# 3X3LEDCube.net
KiCad netlist of a schematic drawn in EAGLE
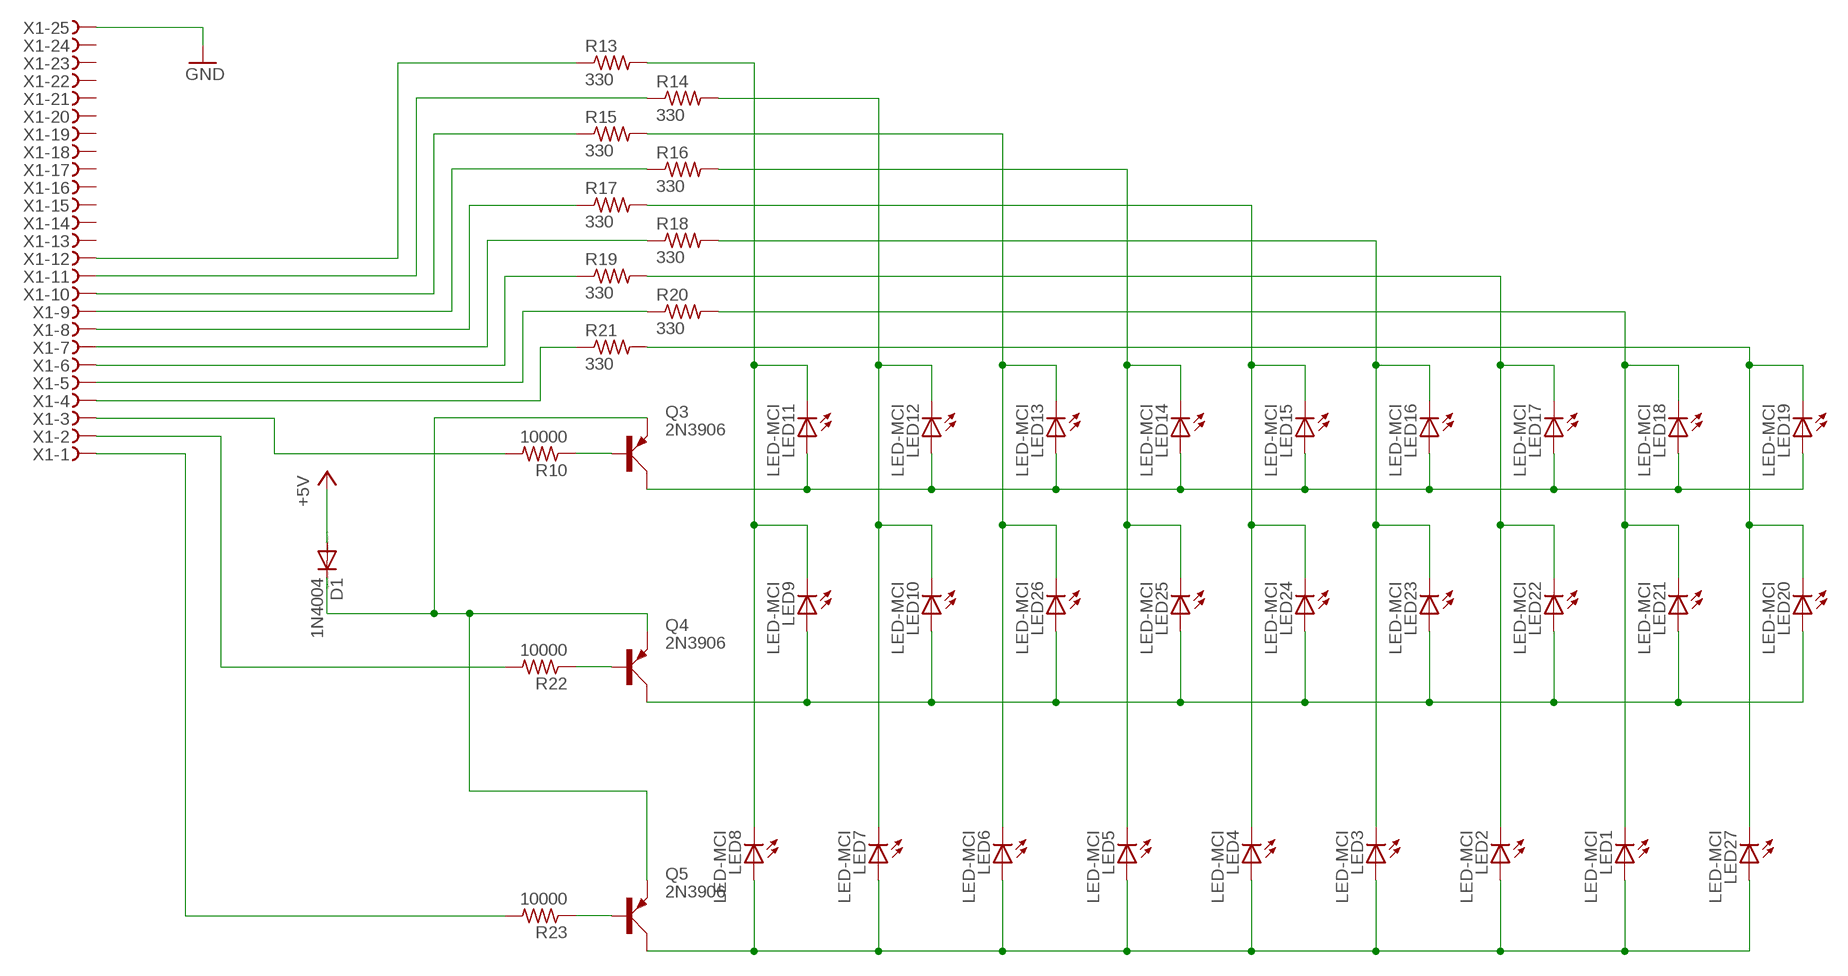
[diagram p0: schematic, sheet 1]

(export (version "E")
  (design (tool "Eeschema 10.0.6"))
  (components
    (comp (ref "D1")
      (value "1N4004")
      (footprint "eagle-import:DO41-10")
      (libsource (lib "eagle-import") (part "1N4004"))
    )
    (comp (ref "LED1")
      (value "LED-MCI")
      (footprint "eagle-import:LED-MCI")
      (libsource (lib "eagle-import") (part "LED-MCI"))
    )
    (comp (ref "LED2")
      (value "LED-MCI")
      (footprint "eagle-import:LED-MCI")
      (libsource (lib "eagle-import") (part "LED-MCI"))
    )
    (comp (ref "LED3")
      (value "LED-MCI")
      (footprint "eagle-import:LED-MCI")
      (libsource (lib "eagle-import") (part "LED-MCI"))
    )
    (comp (ref "LED4")
      (value "LED-MCI")
      (footprint "eagle-import:LED-MCI")
      (libsource (lib "eagle-import") (part "LED-MCI"))
    )
    (comp (ref "LED5")
      (value "LED-MCI")
      (footprint "eagle-import:LED-MCI")
      (libsource (lib "eagle-import") (part "LED-MCI"))
    )
    (comp (ref "LED6")
      (value "LED-MCI")
      (footprint "eagle-import:LED-MCI")
      (libsource (lib "eagle-import") (part "LED-MCI"))
    )
    (comp (ref "LED7")
      (value "LED-MCI")
      (footprint "eagle-import:LED-MCI")
      (libsource (lib "eagle-import") (part "LED-MCI"))
    )
    (comp (ref "LED8")
      (value "LED-MCI")
      (footprint "eagle-import:LED-MCI")
      (libsource (lib "eagle-import") (part "LED-MCI"))
    )
    (comp (ref "LED9")
      (value "LED-MCI")
      (footprint "eagle-import:LED-MCI")
      (libsource (lib "eagle-import") (part "LED-MCI"))
    )
    (comp (ref "LED10")
      (value "LED-MCI")
      (footprint "eagle-import:LED-MCI")
      (libsource (lib "eagle-import") (part "LED-MCI"))
    )
    (comp (ref "LED11")
      (value "LED-MCI")
      (footprint "eagle-import:LED-MCI")
      (libsource (lib "eagle-import") (part "LED-MCI"))
    )
    (comp (ref "LED12")
      (value "LED-MCI")
      (footprint "eagle-import:LED-MCI")
      (libsource (lib "eagle-import") (part "LED-MCI"))
    )
    (comp (ref "LED13")
      (value "LED-MCI")
      (footprint "eagle-import:LED-MCI")
      (libsource (lib "eagle-import") (part "LED-MCI"))
    )
    (comp (ref "LED14")
      (value "LED-MCI")
      (footprint "eagle-import:LED-MCI")
      (libsource (lib "eagle-import") (part "LED-MCI"))
    )
    (comp (ref "LED15")
      (value "LED-MCI")
      (footprint "eagle-import:LED-MCI")
      (libsource (lib "eagle-import") (part "LED-MCI"))
    )
    (comp (ref "LED16")
      (value "LED-MCI")
      (footprint "eagle-import:LED-MCI")
      (libsource (lib "eagle-import") (part "LED-MCI"))
    )
    (comp (ref "LED17")
      (value "LED-MCI")
      (footprint "eagle-import:LED-MCI")
      (libsource (lib "eagle-import") (part "LED-MCI"))
    )
    (comp (ref "LED18")
      (value "LED-MCI")
      (footprint "eagle-import:LED-MCI")
      (libsource (lib "eagle-import") (part "LED-MCI"))
    )
    (comp (ref "LED19")
      (value "LED-MCI")
      (footprint "eagle-import:LED-MCI")
      (libsource (lib "eagle-import") (part "LED-MCI"))
    )
    (comp (ref "LED20")
      (value "LED-MCI")
      (footprint "eagle-import:LED-MCI")
      (libsource (lib "eagle-import") (part "LED-MCI"))
    )
    (comp (ref "LED21")
      (value "LED-MCI")
      (footprint "eagle-import:LED-MCI")
      (libsource (lib "eagle-import") (part "LED-MCI"))
    )
    (comp (ref "LED22")
      (value "LED-MCI")
      (footprint "eagle-import:LED-MCI")
      (libsource (lib "eagle-import") (part "LED-MCI"))
    )
    (comp (ref "LED23")
      (value "LED-MCI")
      (footprint "eagle-import:LED-MCI")
      (libsource (lib "eagle-import") (part "LED-MCI"))
    )
    (comp (ref "LED24")
      (value "LED-MCI")
      (footprint "eagle-import:LED-MCI")
      (libsource (lib "eagle-import") (part "LED-MCI"))
    )
    (comp (ref "LED25")
      (value "LED-MCI")
      (footprint "eagle-import:LED-MCI")
      (libsource (lib "eagle-import") (part "LED-MCI"))
    )
    (comp (ref "LED26")
      (value "LED-MCI")
      (footprint "eagle-import:LED-MCI")
      (libsource (lib "eagle-import") (part "LED-MCI"))
    )
    (comp (ref "LED27")
      (value "LED-MCI")
      (footprint "eagle-import:LED-MCI")
      (libsource (lib "eagle-import") (part "LED-MCI"))
    )
    (comp (ref "Q3")
      (value "2N3906")
      (footprint "eagle-import:TO92D")
      (libsource (lib "eagle-import") (part "2N3906"))
    )
    (comp (ref "Q4")
      (value "2N3906")
      (footprint "eagle-import:TO92D")
      (libsource (lib "eagle-import") (part "2N3906"))
    )
    (comp (ref "Q5")
      (value "2N3906")
      (footprint "eagle-import:TO92D")
      (libsource (lib "eagle-import") (part "2N3906"))
    )
    (comp (ref "R10")
      (value "10000")
      (footprint "eagle-import:RESISTOR-MCI")
      (libsource (lib "eagle-import") (part "RESISTOR-MCI"))
    )
    (comp (ref "R13")
      (value "330")
      (footprint "eagle-import:RESISTOR-MCI")
      (libsource (lib "eagle-import") (part "RESISTOR-MCI"))
    )
    (comp (ref "R14")
      (value "330")
      (footprint "eagle-import:RESISTOR-MCI")
      (libsource (lib "eagle-import") (part "RESISTOR-MCI"))
    )
    (comp (ref "R15")
      (value "330")
      (footprint "eagle-import:RESISTOR-MCI")
      (libsource (lib "eagle-import") (part "RESISTOR-MCI"))
    )
    (comp (ref "R16")
      (value "330")
      (footprint "eagle-import:RESISTOR-MCI")
      (libsource (lib "eagle-import") (part "RESISTOR-MCI"))
    )
    (comp (ref "R17")
      (value "330")
      (footprint "eagle-import:RESISTOR-MCI")
      (libsource (lib "eagle-import") (part "RESISTOR-MCI"))
    )
    (comp (ref "R18")
      (value "330")
      (footprint "eagle-import:RESISTOR-MCI")
      (libsource (lib "eagle-import") (part "RESISTOR-MCI"))
    )
    (comp (ref "R19")
      (value "330")
      (footprint "eagle-import:RESISTOR-MCI")
      (libsource (lib "eagle-import") (part "RESISTOR-MCI"))
    )
    (comp (ref "R20")
      (value "330")
      (footprint "eagle-import:RESISTOR-MCI")
      (libsource (lib "eagle-import") (part "RESISTOR-MCI"))
    )
    (comp (ref "R21")
      (value "330")
      (footprint "eagle-import:RESISTOR-MCI")
      (libsource (lib "eagle-import") (part "RESISTOR-MCI"))
    )
    (comp (ref "R22")
      (value "10000")
      (footprint "eagle-import:RESISTOR-MCI")
      (libsource (lib "eagle-import") (part "RESISTOR-MCI"))
    )
    (comp (ref "R23")
      (value "10000")
      (footprint "eagle-import:RESISTOR-MCI")
      (libsource (lib "eagle-import") (part "RESISTOR-MCI"))
    )
    (comp (ref "X1")
      (value "F25.590S")
      (footprint "eagle-import:177-025-FEMALE")
      (libsource (lib "eagle-import") (part "F25?S.590"))
    )
  )
  (nets
    (net (code "1") (name "+5V") (class "Default")
      (node (ref "D1") (pin "A") (pinfunction "A_A") (pintype "passive"))
    )
    (net (code "2") (name "GND") (class "Default")
      (node (ref "X1") (pin "25") (pinfunction "F_25") (pintype "passive"))
    )
    (net (code "3") (name "Net-(D1-PadC)") (class "Default")
      (node (ref "D1") (pin "C") (pinfunction "C_C") (pintype "passive"))
      (node (ref "Q3") (pin "E") (pinfunction "E_E") (pintype "passive"))
      (node (ref "Q4") (pin "E") (pinfunction "E_E") (pintype "passive"))
      (node (ref "Q5") (pin "E") (pinfunction "E_E") (pintype "passive"))
    )
    (net (code "4") (name "Net-(LED1-A)") (class "Default")
      (node (ref "LED1") (pin "2") (pinfunction "A_2") (pintype "passive"))
      (node (ref "LED2") (pin "2") (pinfunction "A_2") (pintype "passive"))
      (node (ref "LED27") (pin "2") (pinfunction "A_2") (pintype "passive"))
      (node (ref "LED3") (pin "2") (pinfunction "A_2") (pintype "passive"))
      (node (ref "LED4") (pin "2") (pinfunction "A_2") (pintype "passive"))
      (node (ref "LED5") (pin "2") (pinfunction "A_2") (pintype "passive"))
      (node (ref "LED6") (pin "2") (pinfunction "A_2") (pintype "passive"))
      (node (ref "LED7") (pin "2") (pinfunction "A_2") (pintype "passive"))
      (node (ref "LED8") (pin "2") (pinfunction "A_2") (pintype "passive"))
      (node (ref "Q5") (pin "C") (pinfunction "C_C") (pintype "passive"))
    )
    (net (code "5") (name "Net-(LED1-C)") (class "Default")
      (node (ref "LED1") (pin "1") (pinfunction "C_1") (pintype "passive"))
      (node (ref "LED18") (pin "1") (pinfunction "C_1") (pintype "passive"))
      (node (ref "LED21") (pin "1") (pinfunction "C_1") (pintype "passive"))
      (node (ref "R20") (pin "2") (pinfunction "2_2") (pintype "passive"))
    )
    (net (code "6") (name "Net-(LED10-A)") (class "Default")
      (node (ref "LED10") (pin "2") (pinfunction "A_2") (pintype "passive"))
      (node (ref "LED20") (pin "2") (pinfunction "A_2") (pintype "passive"))
      (node (ref "LED21") (pin "2") (pinfunction "A_2") (pintype "passive"))
      (node (ref "LED22") (pin "2") (pinfunction "A_2") (pintype "passive"))
      (node (ref "LED23") (pin "2") (pinfunction "A_2") (pintype "passive"))
      (node (ref "LED24") (pin "2") (pinfunction "A_2") (pintype "passive"))
      (node (ref "LED25") (pin "2") (pinfunction "A_2") (pintype "passive"))
      (node (ref "LED26") (pin "2") (pinfunction "A_2") (pintype "passive"))
      (node (ref "LED9") (pin "2") (pinfunction "A_2") (pintype "passive"))
      (node (ref "Q4") (pin "C") (pinfunction "C_C") (pintype "passive"))
    )
    (net (code "7") (name "Net-(LED10-C)") (class "Default")
      (node (ref "LED10") (pin "1") (pinfunction "C_1") (pintype "passive"))
      (node (ref "LED12") (pin "1") (pinfunction "C_1") (pintype "passive"))
      (node (ref "LED7") (pin "1") (pinfunction "C_1") (pintype "passive"))
      (node (ref "R14") (pin "2") (pinfunction "2_2") (pintype "passive"))
    )
    (net (code "8") (name "Net-(LED11-A)") (class "Default")
      (node (ref "LED11") (pin "1") (pinfunction "C_1") (pintype "passive"))
      (node (ref "LED11") (pin "2") (pinfunction "A_2") (pintype "passive"))
      (node (ref "LED12") (pin "2") (pinfunction "A_2") (pintype "passive"))
      (node (ref "LED13") (pin "2") (pinfunction "A_2") (pintype "passive"))
      (node (ref "LED14") (pin "2") (pinfunction "A_2") (pintype "passive"))
      (node (ref "LED15") (pin "2") (pinfunction "A_2") (pintype "passive"))
      (node (ref "LED16") (pin "2") (pinfunction "A_2") (pintype "passive"))
      (node (ref "LED17") (pin "2") (pinfunction "A_2") (pintype "passive"))
      (node (ref "LED18") (pin "2") (pinfunction "A_2") (pintype "passive"))
      (node (ref "LED19") (pin "2") (pinfunction "A_2") (pintype "passive"))
      (node (ref "LED8") (pin "1") (pinfunction "C_1") (pintype "passive"))
      (node (ref "LED9") (pin "1") (pinfunction "C_1") (pintype "passive"))
      (node (ref "Q3") (pin "C") (pinfunction "C_C") (pintype "passive"))
      (node (ref "R13") (pin "2") (pinfunction "2_2") (pintype "passive"))
    )
    (net (code "9") (name "Net-(LED13-C)") (class "Default")
      (node (ref "LED13") (pin "1") (pinfunction "C_1") (pintype "passive"))
      (node (ref "LED26") (pin "1") (pinfunction "C_1") (pintype "passive"))
      (node (ref "LED6") (pin "1") (pinfunction "C_1") (pintype "passive"))
      (node (ref "R15") (pin "2") (pinfunction "2_2") (pintype "passive"))
    )
    (net (code "10") (name "Net-(LED14-C)") (class "Default")
      (node (ref "LED14") (pin "1") (pinfunction "C_1") (pintype "passive"))
      (node (ref "LED25") (pin "1") (pinfunction "C_1") (pintype "passive"))
      (node (ref "LED5") (pin "1") (pinfunction "C_1") (pintype "passive"))
      (node (ref "R16") (pin "2") (pinfunction "2_2") (pintype "passive"))
    )
    (net (code "11") (name "Net-(LED15-C)") (class "Default")
      (node (ref "LED15") (pin "1") (pinfunction "C_1") (pintype "passive"))
      (node (ref "LED24") (pin "1") (pinfunction "C_1") (pintype "passive"))
      (node (ref "LED4") (pin "1") (pinfunction "C_1") (pintype "passive"))
      (node (ref "R17") (pin "2") (pinfunction "2_2") (pintype "passive"))
    )
    (net (code "12") (name "Net-(LED16-C)") (class "Default")
      (node (ref "LED16") (pin "1") (pinfunction "C_1") (pintype "passive"))
      (node (ref "LED23") (pin "1") (pinfunction "C_1") (pintype "passive"))
      (node (ref "LED3") (pin "1") (pinfunction "C_1") (pintype "passive"))
      (node (ref "R18") (pin "2") (pinfunction "2_2") (pintype "passive"))
    )
    (net (code "13") (name "Net-(LED17-C)") (class "Default")
      (node (ref "LED17") (pin "1") (pinfunction "C_1") (pintype "passive"))
      (node (ref "LED2") (pin "1") (pinfunction "C_1") (pintype "passive"))
      (node (ref "LED22") (pin "1") (pinfunction "C_1") (pintype "passive"))
      (node (ref "R19") (pin "2") (pinfunction "2_2") (pintype "passive"))
    )
    (net (code "14") (name "Net-(LED19-C)") (class "Default")
      (node (ref "LED19") (pin "1") (pinfunction "C_1") (pintype "passive"))
      (node (ref "LED20") (pin "1") (pinfunction "C_1") (pintype "passive"))
      (node (ref "LED27") (pin "1") (pinfunction "C_1") (pintype "passive"))
      (node (ref "R21") (pin "2") (pinfunction "2_2") (pintype "passive"))
    )
    (net (code "15") (name "Net-(Q3-PadB)") (class "Default")
      (node (ref "Q3") (pin "B") (pinfunction "B_B") (pintype "passive"))
      (node (ref "R10") (pin "1") (pinfunction "1_1") (pintype "passive"))
    )
    (net (code "16") (name "Net-(Q4-PadB)") (class "Default")
      (node (ref "Q4") (pin "B") (pinfunction "B_B") (pintype "passive"))
      (node (ref "R22") (pin "1") (pinfunction "1_1") (pintype "passive"))
    )
    (net (code "17") (name "Net-(Q5-PadB)") (class "Default")
      (node (ref "Q5") (pin "B") (pinfunction "B_B") (pintype "passive"))
      (node (ref "R23") (pin "1") (pinfunction "1_1") (pintype "passive"))
    )
    (net (code "18") (name "Net-(X1A-F)") (class "Default")
      (node (ref "R23") (pin "2") (pinfunction "2_2") (pintype "passive"))
      (node (ref "X1") (pin "1") (pinfunction "F_1") (pintype "passive"))
    )
    (net (code "19") (name "Net-(X1B-F)") (class "Default")
      (node (ref "R15") (pin "1") (pinfunction "1_1") (pintype "passive"))
      (node (ref "X1") (pin "10") (pinfunction "F_10") (pintype "passive"))
    )
    (net (code "20") (name "Net-(X1C-F)") (class "Default")
      (node (ref "R14") (pin "1") (pinfunction "1_1") (pintype "passive"))
      (node (ref "X1") (pin "11") (pinfunction "F_11") (pintype "passive"))
    )
    (net (code "21") (name "Net-(X1D-F)") (class "Default")
      (node (ref "R13") (pin "1") (pinfunction "1_1") (pintype "passive"))
      (node (ref "X1") (pin "12") (pinfunction "F_12") (pintype "passive"))
    )
    (net (code "22") (name "Net-(X1L-F)") (class "Default")
      (node (ref "R22") (pin "2") (pinfunction "2_2") (pintype "passive"))
      (node (ref "X1") (pin "2") (pinfunction "F_2") (pintype "passive"))
    )
    (net (code "23") (name "Net-(X1S-F)") (class "Default")
      (node (ref "R10") (pin "2") (pinfunction "2_2") (pintype "passive"))
      (node (ref "X1") (pin "3") (pinfunction "F_3") (pintype "passive"))
    )
    (net (code "24") (name "Net-(X1T-F)") (class "Default")
      (node (ref "R21") (pin "1") (pinfunction "1_1") (pintype "passive"))
      (node (ref "X1") (pin "4") (pinfunction "F_4") (pintype "passive"))
    )
    (net (code "25") (name "Net-(X1U-F)") (class "Default")
      (node (ref "R20") (pin "1") (pinfunction "1_1") (pintype "passive"))
      (node (ref "X1") (pin "5") (pinfunction "F_5") (pintype "passive"))
    )
    (net (code "26") (name "Net-(X1V-F)") (class "Default")
      (node (ref "R19") (pin "1") (pinfunction "1_1") (pintype "passive"))
      (node (ref "X1") (pin "6") (pinfunction "F_6") (pintype "passive"))
    )
    (net (code "27") (name "Net-(X1W-F)") (class "Default")
      (node (ref "R18") (pin "1") (pinfunction "1_1") (pintype "passive"))
      (node (ref "X1") (pin "7") (pinfunction "F_7") (pintype "passive"))
    )
    (net (code "28") (name "Net-(X1X-F)") (class "Default")
      (node (ref "R17") (pin "1") (pinfunction "1_1") (pintype "passive"))
      (node (ref "X1") (pin "8") (pinfunction "F_8") (pintype "passive"))
    )
    (net (code "29") (name "Net-(X1Y-F)") (class "Default")
      (node (ref "R16") (pin "1") (pinfunction "1_1") (pintype "passive"))
      (node (ref "X1") (pin "9") (pinfunction "F_9") (pintype "passive"))
    )
    (net (code "30") (name "unconnected-(X1E-F-Pad13)") (class "Default")
      (node (ref "X1") (pin "13") (pinfunction "F_13") (pintype "passive"))
    )
    (net (code "31") (name "unconnected-(X1F-F-Pad14)") (class "Default")
      (node (ref "X1") (pin "14") (pinfunction "F_14") (pintype "passive"))
    )
    (net (code "32") (name "unconnected-(X1G-F-Pad15)") (class "Default")
      (node (ref "X1") (pin "15") (pinfunction "F_15") (pintype "passive"))
    )
    (net (code "33") (name "unconnected-(X1H-F-Pad16)") (class "Default")
      (node (ref "X1") (pin "16") (pinfunction "F_16") (pintype "passive"))
    )
    (net (code "34") (name "unconnected-(X1I-F-Pad17)") (class "Default")
      (node (ref "X1") (pin "17") (pinfunction "F_17") (pintype "passive"))
    )
    (net (code "35") (name "unconnected-(X1J-F-Pad18)") (class "Default")
      (node (ref "X1") (pin "18") (pinfunction "F_18") (pintype "passive"))
    )
    (net (code "36") (name "unconnected-(X1K-F-Pad19)") (class "Default")
      (node (ref "X1") (pin "19") (pinfunction "F_19") (pintype "passive"))
    )
    (net (code "37") (name "unconnected-(X1M-F-Pad20)") (class "Default")
      (node (ref "X1") (pin "20") (pinfunction "F_20") (pintype "passive"))
    )
    (net (code "38") (name "unconnected-(X1N-F-Pad21)") (class "Default")
      (node (ref "X1") (pin "21") (pinfunction "F_21") (pintype "passive"))
    )
    (net (code "39") (name "unconnected-(X1O-F-Pad22)") (class "Default")
      (node (ref "X1") (pin "22") (pinfunction "F_22") (pintype "passive"))
    )
    (net (code "40") (name "unconnected-(X1P-F-Pad23)") (class "Default")
      (node (ref "X1") (pin "23") (pinfunction "F_23") (pintype "passive"))
    )
    (net (code "41") (name "unconnected-(X1Q-F-Pad24)") (class "Default")
      (node (ref "X1") (pin "24") (pinfunction "F_24") (pintype "passive"))
    )
  )
)
